# LogicPCB.net
KiCad netlist of a schematic drawn in EAGLE
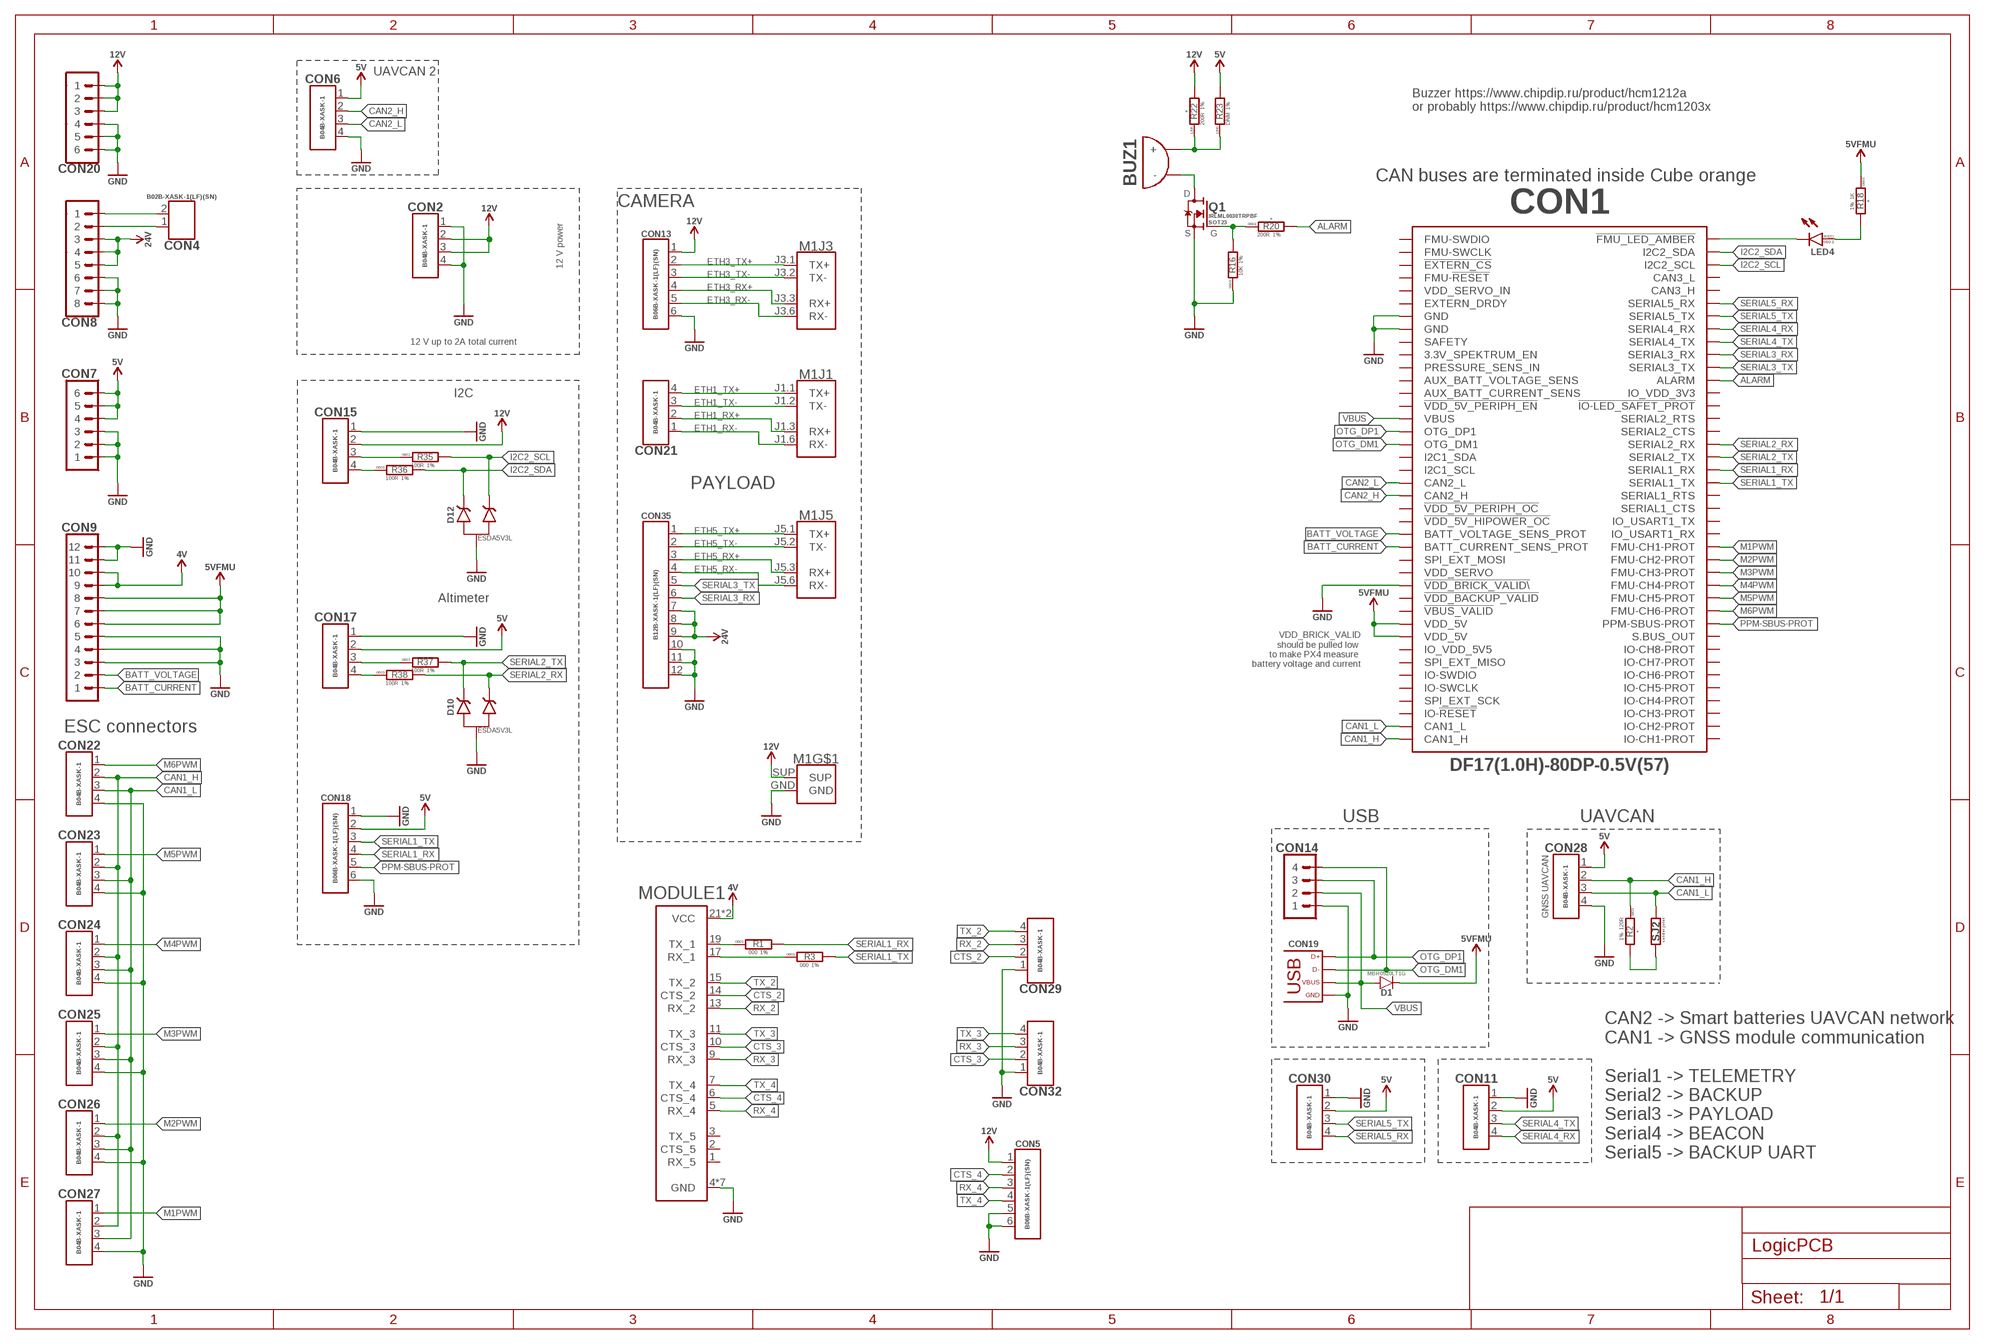
[diagram p0: schematic, sheet 1]

(export (version "E")
  (design (tool "Eeschema 10.0.6"))
  (components
    (comp (ref "BUZ1")
      (value "BUZZER-ЕР-12MM")
      (footprint "eagle-import:BUZZER_12MM")
      (fields (field (name "MANF") "JL World") (field (name "MANF#") "HCM1212A"))
      (libsource (lib "eagle-import") (part "BUZZER-ЕР-12MM"))
    )
    (comp (ref "CON1")
      (value "CUBE_ORANGE_")
      (footprint "eagle-import:CUBE_ORANGE")
      (fields (field (name "MANF#") "DF17(1.0H)-80DP-0.5V(57)") (field (name "MANF") "HIROSE"))
      (libsource (lib "eagle-import") (part "CUBE_ORANGE_"))
    )
    (comp (ref "CON2")
      (value "CON-4P-JST-XA")
      (footprint "eagle-import:B04B-XASK-1")
      (fields (field (name "MANF#") "B04B-XASK-1") (field (name "MANF") "JST Sales America"))
      (libsource (lib "eagle-import") (part "CON-4P-JST-XA"))
    )
    (comp (ref "CON4")
      (value "CON-2P-JST-XA")
      (footprint "eagle-import:B02B-XASK-1")
      (fields (field (name "MANF#") "B02B-XASK-1(LF)(SN)") (field (name "MANF") "JST Sales America"))
      (libsource (lib "eagle-import") (part "CON-2P-JST-XA"))
    )
    (comp (ref "CON5")
      (value "CON-6P-JST-XA")
      (footprint "eagle-import:B06B-XASK-1")
      (fields (field (name "MANF#") "B06B-XASK-1(LF)(SN)") (field (name "MANF") "JST Sales America"))
      (libsource (lib "eagle-import") (part "CON-6P-JST-XA"))
    )
    (comp (ref "CON6")
      (value "CON-4P-JST-XA")
      (footprint "eagle-import:B04B-XASK-1")
      (fields (field (name "MANF#") "B04B-XASK-1") (field (name "MANF") "JST Sales America"))
      (libsource (lib "eagle-import") (part "CON-4P-JST-XA"))
    )
    (comp (ref "CON7")
      (value "PINHEAD_1X06-2.54")
      (footprint "eagle-import:1X06-PTH-2.54")
      (libsource (lib "eagle-import") (part "PINHEAD_1X06-2.54"))
    )
    (comp (ref "CON8")
      (value "PINHEAD_1X08-2.54")
      (footprint "eagle-import:1X08-PTH-2.54")
      (libsource (lib "eagle-import") (part "PINHEAD_1X08-2.54"))
    )
    (comp (ref "CON9")
      (value "PINHEAD_1X12-2.54")
      (footprint "eagle-import:1X12-PTH-2.54")
      (libsource (lib "eagle-import") (part "PINHEAD_1X12-2.54"))
    )
    (comp (ref "CON11")
      (value "CON-4P-JST-XA")
      (footprint "eagle-import:B04B-XASK-1")
      (fields (field (name "MANF#") "B04B-XASK-1") (field (name "MANF") "JST Sales America"))
      (libsource (lib "eagle-import") (part "CON-4P-JST-XA"))
    )
    (comp (ref "CON13")
      (value "CON-6P-JST-XA")
      (footprint "eagle-import:B06B-XASK-1")
      (fields (field (name "MANF#") "B06B-XASK-1(LF)(SN)") (field (name "MANF") "JST Sales America"))
      (libsource (lib "eagle-import") (part "CON-6P-JST-XA"))
    )
    (comp (ref "CON14")
      (value "PINHEAD_1X04-2.54")
      (footprint "eagle-import:1X04-PTH-2.54")
      (libsource (lib "eagle-import") (part "PINHEAD_1X04-2.54"))
    )
    (comp (ref "CON15")
      (value "CON-4P-JST-XA")
      (footprint "eagle-import:B04B-XASK-1")
      (fields (field (name "MANF#") "B04B-XASK-1") (field (name "MANF") "JST Sales America"))
      (libsource (lib "eagle-import") (part "CON-4P-JST-XA"))
    )
    (comp (ref "CON17")
      (value "CON-4P-JST-XA")
      (footprint "eagle-import:B04B-XASK-1")
      (fields (field (name "MANF#") "B04B-XASK-1") (field (name "MANF") "JST Sales America"))
      (libsource (lib "eagle-import") (part "CON-4P-JST-XA"))
    )
    (comp (ref "CON18")
      (value "CON-6P-JST-XA")
      (footprint "eagle-import:B06B-XASK-1")
      (fields (field (name "MANF#") "B06B-XASK-1(LF)(SN)") (field (name "MANF") "JST Sales America"))
      (libsource (lib "eagle-import") (part "CON-6P-JST-XA"))
    )
    (comp (ref "CON19")
      (value "USB-TYPE-C-VERT-PROD")
      (footprint "eagle-import:2047110001-PROD")
      (fields (field (name "MANF") "Molex"))
      (libsource (lib "eagle-import") (part "USB-TYPE-C-VERT-PROD"))
    )
    (comp (ref "CON20")
      (value "PINHEAD_1X06-2.54")
      (footprint "eagle-import:1X06-PTH-2.54")
      (libsource (lib "eagle-import") (part "PINHEAD_1X06-2.54"))
    )
    (comp (ref "CON21")
      (value "CON-4P-JST-XA")
      (footprint "eagle-import:B04B-XASK-1")
      (fields (field (name "MANF#") "B04B-XASK-1") (field (name "MANF") "JST Sales America"))
      (libsource (lib "eagle-import") (part "CON-4P-JST-XA"))
    )
    (comp (ref "CON22")
      (value "CON-4P-JST-XA")
      (footprint "eagle-import:B04B-XASK-1")
      (fields (field (name "MANF#") "B04B-XASK-1") (field (name "MANF") "JST Sales America"))
      (libsource (lib "eagle-import") (part "CON-4P-JST-XA"))
    )
    (comp (ref "CON23")
      (value "CON-4P-JST-XA")
      (footprint "eagle-import:B04B-XASK-1")
      (fields (field (name "MANF#") "B04B-XASK-1") (field (name "MANF") "JST Sales America"))
      (libsource (lib "eagle-import") (part "CON-4P-JST-XA"))
    )
    (comp (ref "CON24")
      (value "CON-4P-JST-XA")
      (footprint "eagle-import:B04B-XASK-1")
      (fields (field (name "MANF#") "B04B-XASK-1") (field (name "MANF") "JST Sales America"))
      (libsource (lib "eagle-import") (part "CON-4P-JST-XA"))
    )
    (comp (ref "CON25")
      (value "CON-4P-JST-XA")
      (footprint "eagle-import:B04B-XASK-1")
      (fields (field (name "MANF#") "B04B-XASK-1") (field (name "MANF") "JST Sales America"))
      (libsource (lib "eagle-import") (part "CON-4P-JST-XA"))
    )
    (comp (ref "CON26")
      (value "CON-4P-JST-XA")
      (footprint "eagle-import:B04B-XASK-1")
      (fields (field (name "MANF#") "B04B-XASK-1") (field (name "MANF") "JST Sales America"))
      (libsource (lib "eagle-import") (part "CON-4P-JST-XA"))
    )
    (comp (ref "CON27")
      (value "CON-4P-JST-XA")
      (footprint "eagle-import:B04B-XASK-1")
      (fields (field (name "MANF#") "B04B-XASK-1") (field (name "MANF") "JST Sales America"))
      (libsource (lib "eagle-import") (part "CON-4P-JST-XA"))
    )
    (comp (ref "CON28")
      (value "CON-4P-JST-XA")
      (footprint "eagle-import:B04B-XASK-1")
      (fields (field (name "MANF#") "B04B-XASK-1") (field (name "MANF") "JST Sales America"))
      (libsource (lib "eagle-import") (part "CON-4P-JST-XA"))
    )
    (comp (ref "CON29")
      (value "CON-4P-JST-XA")
      (footprint "eagle-import:B04B-XASK-1")
      (fields (field (name "MANF#") "B04B-XASK-1") (field (name "MANF") "JST Sales America"))
      (libsource (lib "eagle-import") (part "CON-4P-JST-XA"))
    )
    (comp (ref "CON30")
      (value "CON-4P-JST-XA")
      (footprint "eagle-import:B04B-XASK-1")
      (fields (field (name "MANF#") "B04B-XASK-1") (field (name "MANF") "JST Sales America"))
      (libsource (lib "eagle-import") (part "CON-4P-JST-XA"))
    )
    (comp (ref "CON32")
      (value "CON-4P-JST-XA")
      (footprint "eagle-import:B04B-XASK-1")
      (fields (field (name "MANF#") "B04B-XASK-1") (field (name "MANF") "JST Sales America"))
      (libsource (lib "eagle-import") (part "CON-4P-JST-XA"))
    )
    (comp (ref "CON35")
      (value "CON-12P-JST-XA")
      (footprint "eagle-import:B12B-XASK-1")
      (fields (field (name "MANF#") "B12B-XASK-1(LF)(SN)") (field (name "MANF") "JST Sales America"))
      (libsource (lib "eagle-import") (part "CON-12P-JST-XA"))
    )
    (comp (ref "D1")
      (value "MBR0520L-SOD123")
      (footprint "eagle-import:SOD123")
      (fields (field (name "MANF#") "MBR0520LT1G") (field (name "MANF") "ON Semiconductor"))
      (libsource (lib "eagle-import") (part "MBR0520L-SOD123"))
    )
    (comp (ref "D10")
      (value "ESDA5V3L")
      (footprint "eagle-import:SOT23B-3")
      (fields (field (name "MANF#") "ESDA5V3L") (field (name "MANF") "STMicroelectronics"))
      (libsource (lib "eagle-import") (part "ESDA5V3L"))
    )
    (comp (ref "D12")
      (value "ESDA5V3L")
      (footprint "eagle-import:SOT23B-3")
      (fields (field (name "MANF#") "ESDA5V3L") (field (name "MANF") "STMicroelectronics"))
      (libsource (lib "eagle-import") (part "ESDA5V3L"))
    )
    (comp (ref "LED4")
      (value "LED-0603")
      (footprint "eagle-import:LED0603")
      (fields
        (field (name "PACKAGE") "0603")
        (field (name "COLOR") "RED")
        (field (name "LCSC#") "C2286")
        (field (name "MANF") "Hubei KENTO Elec")
        (field (name "MANF#") "KT-0603R")
      )
      (libsource (lib "eagle-import") (part "LED-0603"))
    )
    (comp (ref "M1")
      (value "05G_ETHERNET_SWITCH")
      (footprint "eagle-import:05G_ETH_SWITCH")
      (libsource (lib "eagle-import") (part "05G_ETHERNET_SWITCH"))
    )
    (comp (ref "MODULE1")
      (value "MODEM_CARRIER")
      (footprint "eagle-import:MODEM_CARRIER")
      (libsource (lib "eagle-import") (part "MODEM_CARRIER"))
    )
    (comp (ref "Q1")
      (value "IRLML0030")
      (footprint "eagle-import:SOT23")
      (fields
        (field (name "MANF#") "IRLML0030TRPBF")
        (field (name "PACKAGE") "SOT23")
        (field (name "MANF") "Infineon Technologies")
      )
      (libsource (lib "eagle-import") (part "IRLML0030"))
    )
    (comp (ref "R1")
      (value "000")
      (footprint "eagle-import:R0603")
      (fields (field (name "PACKAGE") "0603") (field (name "TOLERANCE") "1%"))
      (libsource (lib "eagle-import") (part "R-0603-1%"))
    )
    (comp (ref "R2")
      (value "120R")
      (footprint "eagle-import:R0603")
      (fields
        (field (name "PACKAGE") "0603")
        (field (name "TOLERANCE") "1%")
        (field (name "ALLOCATED") "+")
        (field (name "LCSC#") "C22787")
        (field (name "MANF") "UNI-ROYAL(Uniroyal Elec)")
        (field (name "MANF#") "0603WAF1200T5E")
      )
      (libsource (lib "eagle-import") (part "R-0603-1%"))
    )
    (comp (ref "R3")
      (value "000")
      (footprint "eagle-import:R0603")
      (fields (field (name "PACKAGE") "0603") (field (name "TOLERANCE") "1%"))
      (libsource (lib "eagle-import") (part "R-0603-1%"))
    )
    (comp (ref "R16")
      (value "10K")
      (footprint "eagle-import:R0603")
      (fields (field (name "PACKAGE") "0603") (field (name "TOLERANCE") "1%"))
      (libsource (lib "eagle-import") (part "R-0603-1%"))
    )
    (comp (ref "R18")
      (value "1K")
      (footprint "eagle-import:R0603")
      (fields
        (field (name "PACKAGE") "0603")
        (field (name "TOLERANCE") "1%")
        (field (name "ALLOCATED") "+")
        (field (name "LCSC#") "C21190")
        (field (name "MANF") "UNI-ROYAL(Uniroyal Elec)")
        (field (name "MANF#") "0603WAF1001T5E")
      )
      (libsource (lib "eagle-import") (part "R-0603-1%"))
    )
    (comp (ref "R20")
      (value "200R")
      (footprint "eagle-import:R0603")
      (fields
        (field (name "PACKAGE") "0603")
        (field (name "TOLERANCE") "1%")
        (field (name "ALLOCATED") "+")
        (field (name "LCSC#") "C21190")
        (field (name "MANF") "UNI-ROYAL(Uniroyal Elec)")
        (field (name "MANF#") "0603WAF1001T5E")
      )
      (libsource (lib "eagle-import") (part "R-0603-1%"))
    )
    (comp (ref "R22")
      (value "200R")
      (footprint "eagle-import:R1206")
      (fields
        (field (name "PACKAGE") "1206")
        (field (name "TOLERANCE") "1%")
        (field (name "ALLOCATED") "+")
        (field (name "LCSC#") "C25361")
        (field (name "MANF") "UNI-ROYAL")
        (field (name "MANF#") "1206W4J0201T5E")
      )
      (libsource (lib "eagle-import") (part "R-1206-1%"))
    )
    (comp (ref "R23")
      (value "DNM")
      (footprint "eagle-import:R1206")
      (fields (field (name "PACKAGE") "1206") (field (name "TOLERANCE") "1%"))
      (libsource (lib "eagle-import") (part "R-1206-1%"))
    )
    (comp (ref "R35")
      (value "100R")
      (footprint "eagle-import:R0603")
      (fields (field (name "PACKAGE") "0603") (field (name "TOLERANCE") "1%"))
      (libsource (lib "eagle-import") (part "R-0603-1%"))
    )
    (comp (ref "R36")
      (value "100R")
      (footprint "eagle-import:R0603")
      (fields (field (name "PACKAGE") "0603") (field (name "TOLERANCE") "1%"))
      (libsource (lib "eagle-import") (part "R-0603-1%"))
    )
    (comp (ref "R37")
      (value "100R")
      (footprint "eagle-import:R0603")
      (fields (field (name "PACKAGE") "0603") (field (name "TOLERANCE") "1%"))
      (libsource (lib "eagle-import") (part "R-0603-1%"))
    )
    (comp (ref "R38")
      (value "100R")
      (footprint "eagle-import:R0603")
      (fields (field (name "PACKAGE") "0603") (field (name "TOLERANCE") "1%"))
      (libsource (lib "eagle-import") (part "R-0603-1%"))
    )
    (comp (ref "SJ2")
      (value "SOLDER_JOINT-SJ1")
      (footprint "eagle-import:RES_0")
      (libsource (lib "eagle-import") (part "SOLDER_JOINT-SJ1"))
    )
  )
  (nets
    (net (code "1") (name "/ETH1_RX+") (class "Default")
      (node (ref "CON21") (pin "2") (pinfunction "2_2") (pintype "bidirectional"))
      (node (ref "M1") (pin "J1.3") (pinfunction "RX+_J1.3") (pintype "bidirectional"))
    )
    (net (code "2") (name "/ETH1_RX-") (class "Default")
      (node (ref "CON21") (pin "1") (pinfunction "1_1") (pintype "bidirectional"))
      (node (ref "M1") (pin "J1.6") (pinfunction "RX-_J1.6") (pintype "bidirectional"))
    )
    (net (code "3") (name "/ETH1_TX+") (class "Default")
      (node (ref "CON21") (pin "4") (pinfunction "4_4") (pintype "bidirectional"))
      (node (ref "M1") (pin "J1.1") (pinfunction "TX+_J1.1") (pintype "bidirectional"))
    )
    (net (code "4") (name "/ETH1_TX-") (class "Default")
      (node (ref "CON21") (pin "3") (pinfunction "3_3") (pintype "bidirectional"))
      (node (ref "M1") (pin "J1.2") (pinfunction "TX-_J1.2") (pintype "bidirectional"))
    )
    (net (code "5") (name "/ETH3_RX+") (class "Default")
      (node (ref "CON13") (pin "4") (pinfunction "4_4") (pintype "bidirectional"))
      (node (ref "M1") (pin "J3.3") (pinfunction "RX+_J3.3") (pintype "bidirectional"))
    )
    (net (code "6") (name "/ETH3_RX-") (class "Default")
      (node (ref "CON13") (pin "5") (pinfunction "5_5") (pintype "bidirectional"))
      (node (ref "M1") (pin "J3.6") (pinfunction "RX-_J3.6") (pintype "bidirectional"))
    )
    (net (code "7") (name "/ETH3_TX+") (class "Default")
      (node (ref "CON13") (pin "2") (pinfunction "2_2") (pintype "bidirectional"))
      (node (ref "M1") (pin "J3.1") (pinfunction "TX+_J3.1") (pintype "bidirectional"))
    )
    (net (code "8") (name "/ETH3_TX-") (class "Default")
      (node (ref "CON13") (pin "3") (pinfunction "3_3") (pintype "bidirectional"))
      (node (ref "M1") (pin "J3.2") (pinfunction "TX-_J3.2") (pintype "bidirectional"))
    )
    (net (code "9") (name "/ETH5_RX+") (class "Default")
      (node (ref "CON35") (pin "3") (pinfunction "3_3") (pintype "bidirectional"))
      (node (ref "M1") (pin "J5.3") (pinfunction "RX+_J5.3") (pintype "bidirectional"))
    )
    (net (code "10") (name "/ETH5_RX-") (class "Default")
      (node (ref "CON35") (pin "4") (pinfunction "4_4") (pintype "bidirectional"))
      (node (ref "M1") (pin "J5.6") (pinfunction "RX-_J5.6") (pintype "bidirectional"))
    )
    (net (code "11") (name "/ETH5_TX+") (class "Default")
      (node (ref "CON35") (pin "1") (pinfunction "1_1") (pintype "bidirectional"))
      (node (ref "M1") (pin "J5.1") (pinfunction "TX+_J5.1") (pintype "bidirectional"))
    )
    (net (code "12") (name "/ETH5_TX-") (class "Default")
      (node (ref "CON35") (pin "2") (pinfunction "2_2") (pintype "bidirectional"))
      (node (ref "M1") (pin "J5.2") (pinfunction "TX-_J5.2") (pintype "bidirectional"))
    )
    (net (code "13") (name "4V") (class "Default")
      (node (ref "CON9") (pin "10") (pinfunction "10_10") (pintype "passive"))
      (node (ref "CON9") (pin "9") (pinfunction "9_9") (pintype "passive"))
      (node (ref "MODULE1") (pin "21") (pinfunction "VCC_21") (pintype "bidirectional"))
      (node (ref "MODULE1") (pin "23") (pinfunction "VCC_23") (pintype "bidirectional"))
    )
    (net (code "14") (name "5V") (class "Default")
      (node (ref "CON11") (pin "2") (pinfunction "2_2") (pintype "bidirectional"))
      (node (ref "CON17") (pin "2") (pinfunction "2_2") (pintype "bidirectional"))
      (node (ref "CON18") (pin "2") (pinfunction "2_2") (pintype "bidirectional"))
      (node (ref "CON28") (pin "1") (pinfunction "1_1") (pintype "bidirectional"))
      (node (ref "CON30") (pin "2") (pinfunction "2_2") (pintype "bidirectional"))
      (node (ref "CON6") (pin "1") (pinfunction "1_1") (pintype "bidirectional"))
      (node (ref "CON7") (pin "4") (pinfunction "4_4") (pintype "passive"))
      (node (ref "CON7") (pin "5") (pinfunction "5_5") (pintype "passive"))
      (node (ref "CON7") (pin "6") (pinfunction "6_6") (pintype "passive"))
      (node (ref "R23") (pin "P$2") (pinfunction "2_P$2") (pintype "passive"))
    )
    (net (code "15") (name "5VFMU") (class "Default")
      (node (ref "CON1") (pin "61") (pinfunction "VDD_5V_61") (pintype "bidirectional"))
      (node (ref "CON1") (pin "63") (pinfunction "VDD_5V_63") (pintype "bidirectional"))
      (node (ref "CON9") (pin "6") (pinfunction "6_6") (pintype "passive"))
      (node (ref "CON9") (pin "7") (pinfunction "7_7") (pintype "passive"))
      (node (ref "CON9") (pin "8") (pinfunction "8_8") (pintype "passive"))
      (node (ref "D1") (pin "C") (pinfunction "C_C") (pintype "passive"))
      (node (ref "R18") (pin "1") (pinfunction "1_1") (pintype "passive"))
    )
    (net (code "16") (name "12V") (class "Default")
      (node (ref "CON13") (pin "1") (pinfunction "1_1") (pintype "bidirectional"))
      (node (ref "CON15") (pin "2") (pinfunction "2_2") (pintype "bidirectional"))
      (node (ref "CON2") (pin "2") (pinfunction "2_2") (pintype "bidirectional"))
      (node (ref "CON2") (pin "3") (pinfunction "3_3") (pintype "bidirectional"))
      (node (ref "CON20") (pin "1") (pinfunction "1_1") (pintype "passive"))
      (node (ref "CON20") (pin "2") (pinfunction "2_2") (pintype "passive"))
      (node (ref "CON20") (pin "3") (pinfunction "3_3") (pintype "passive"))
      (node (ref "CON5") (pin "1") (pinfunction "1_1") (pintype "bidirectional"))
      (node (ref "M1") (pin "SUP") (pinfunction "SUP_SUP") (pintype "bidirectional"))
      (node (ref "R22") (pin "P$2") (pinfunction "2_P$2") (pintype "passive"))
    )
    (net (code "17") (name "24V") (class "Default")
      (node (ref "CON35") (pin "7") (pinfunction "7_7") (pintype "bidirectional"))
      (node (ref "CON35") (pin "8") (pinfunction "8_8") (pintype "bidirectional"))
      (node (ref "CON35") (pin "9") (pinfunction "9_9") (pintype "bidirectional"))
      (node (ref "CON8") (pin "3") (pinfunction "3_3") (pintype "passive"))
      (node (ref "CON8") (pin "4") (pinfunction "4_4") (pintype "passive"))
      (node (ref "CON8") (pin "5") (pinfunction "5_5") (pintype "passive"))
    )
    (net (code "18") (name "ALARM") (class "Default")
      (node (ref "CON1") (pin "24") (pinfunction "ALARM_24") (pintype "bidirectional"))
      (node (ref "R20") (pin "2") (pinfunction "2_2") (pintype "passive"))
    )
    (net (code "19") (name "BATT_CURRENT") (class "Default")
      (node (ref "CON1") (pin "49") (pinfunction "BATT_CURRENT_SENS_PROT_49") (pintype "bidirectional"))
      (node (ref "CON9") (pin "1") (pinfunction "1_1") (pintype "passive"))
    )
    (net (code "20") (name "BATT_VOLTAGE") (class "Default")
      (node (ref "CON1") (pin "47") (pinfunction "BATT_VOLTAGE_SENS_PROT_47") (pintype "bidirectional"))
      (node (ref "CON9") (pin "2") (pinfunction "2_2") (pintype "passive"))
    )
    (net (code "21") (name "CAN1_H") (class "Default")
      (node (ref "CON1") (pin "79") (pinfunction "CAN1_H_79") (pintype "bidirectional"))
      (node (ref "CON22") (pin "2") (pinfunction "2_2") (pintype "bidirectional"))
      (node (ref "CON23") (pin "2") (pinfunction "2_2") (pintype "bidirectional"))
      (node (ref "CON24") (pin "2") (pinfunction "2_2") (pintype "bidirectional"))
      (node (ref "CON25") (pin "2") (pinfunction "2_2") (pintype "bidirectional"))
      (node (ref "CON26") (pin "2") (pinfunction "2_2") (pintype "bidirectional"))
      (node (ref "CON27") (pin "2") (pinfunction "2_2") (pintype "bidirectional"))
      (node (ref "CON28") (pin "2") (pinfunction "2_2") (pintype "bidirectional"))
      (node (ref "R2") (pin "1") (pinfunction "1_1") (pintype "passive"))
    )
    (net (code "22") (name "CAN1_L") (class "Default")
      (node (ref "CON1") (pin "77") (pinfunction "CAN1_L_77") (pintype "bidirectional"))
      (node (ref "CON22") (pin "3") (pinfunction "3_3") (pintype "bidirectional"))
      (node (ref "CON23") (pin "3") (pinfunction "3_3") (pintype "bidirectional"))
      (node (ref "CON24") (pin "3") (pinfunction "3_3") (pintype "bidirectional"))
      (node (ref "CON25") (pin "3") (pinfunction "3_3") (pintype "bidirectional"))
      (node (ref "CON26") (pin "3") (pinfunction "3_3") (pintype "bidirectional"))
      (node (ref "CON27") (pin "3") (pinfunction "3_3") (pintype "bidirectional"))
      (node (ref "CON28") (pin "3") (pinfunction "3_3") (pintype "bidirectional"))
      (node (ref "SJ2") (pin "2") (pinfunction "2_2") (pintype "passive"))
    )
    (net (code "23") (name "CAN2_H") (class "Default")
      (node (ref "CON1") (pin "41") (pinfunction "CAN2_H_41") (pintype "bidirectional"))
      (node (ref "CON6") (pin "2") (pinfunction "2_2") (pintype "bidirectional"))
    )
    (net (code "24") (name "CAN2_L") (class "Default")
      (node (ref "CON1") (pin "39") (pinfunction "CAN2_L_39") (pintype "bidirectional"))
      (node (ref "CON6") (pin "3") (pinfunction "3_3") (pintype "bidirectional"))
    )
    (net (code "25") (name "CTS_2") (class "Default")
      (node (ref "CON29") (pin "2") (pinfunction "2_2") (pintype "bidirectional"))
      (node (ref "MODULE1") (pin "14") (pinfunction "CTS_2_14") (pintype "bidirectional"))
    )
    (net (code "26") (name "CTS_3") (class "Default")
      (node (ref "CON32") (pin "2") (pinfunction "2_2") (pintype "bidirectional"))
      (node (ref "MODULE1") (pin "10") (pinfunction "CTS_3_10") (pintype "bidirectional"))
    )
    (net (code "27") (name "CTS_4") (class "Default")
      (node (ref "CON5") (pin "2") (pinfunction "2_2") (pintype "bidirectional"))
      (node (ref "MODULE1") (pin "6") (pinfunction "CTS_4_6") (pintype "bidirectional"))
    )
    (net (code "28") (name "GND") (class "Default")
      (node (ref "CON1") (pin "13") (pinfunction "GND_13") (pintype "bidirectional"))
      (node (ref "CON1") (pin "15") (pinfunction "GND_15") (pintype "bidirectional"))
      (node (ref "CON1") (pin "55") (pinfunction "~{VDD_BRICK_VALID\\}_55") (pintype "bidirectional"))
      (node (ref "CON11") (pin "1") (pinfunction "1_1") (pintype "bidirectional"))
      (node (ref "CON13") (pin "6") (pinfunction "6_6") (pintype "bidirectional"))
      (node (ref "CON14") (pin "1") (pinfunction "1_1") (pintype "passive"))
      (node (ref "CON15") (pin "1") (pinfunction "1_1") (pintype "bidirectional"))
      (node (ref "CON17") (pin "1") (pinfunction "1_1") (pintype "bidirectional"))
      (node (ref "CON18") (pin "1") (pinfunction "1_1") (pintype "bidirectional"))
      (node (ref "CON18") (pin "6") (pinfunction "6_6") (pintype "bidirectional"))
      (node (ref "CON19") (pin "A1") (pinfunction "GND_A1") (pintype "bidirectional"))
      (node (ref "CON19") (pin "A12") (pinfunction "GND_A12") (pintype "bidirectional"))
      (node (ref "CON19") (pin "B1") (pinfunction "GND_B1") (pintype "bidirectional"))
      (node (ref "CON19") (pin "B12") (pinfunction "GND_B12") (pintype "bidirectional"))
      (node (ref "CON19") (pin "G1") (pinfunction "GND_G1") (pintype "bidirectional"))
      (node (ref "CON19") (pin "G10") (pinfunction "GND_G10") (pintype "bidirectional"))
      (node (ref "CON19") (pin "G2") (pinfunction "GND_G2") (pintype "bidirectional"))
      (node (ref "CON19") (pin "G4") (pinfunction "GND_G4") (pintype "bidirectional"))
      (node (ref "CON19") (pin "G5") (pinfunction "GND_G5") (pintype "bidirectional"))
      (node (ref "CON19") (pin "G7") (pinfunction "GND_G7") (pintype "bidirectional"))
      (node (ref "CON19") (pin "G8") (pinfunction "GND_G8") (pintype "bidirectional"))
      (node (ref "CON19") (pin "G9") (pinfunction "GND_G9") (pintype "bidirectional"))
      (node (ref "CON19") (pin "P$1") (pinfunction "GND_P$1") (pintype "bidirectional"))
      (node (ref "CON19") (pin "P$2") (pinfunction "GND_P$2") (pintype "bidirectional"))
      (node (ref "CON2") (pin "1") (pinfunction "1_1") (pintype "bidirectional"))
      (node (ref "CON2") (pin "4") (pinfunction "4_4") (pintype "bidirectional"))
      (node (ref "CON20") (pin "4") (pinfunction "4_4") (pintype "passive"))
      (node (ref "CON20") (pin "5") (pinfunction "5_5") (pintype "passive"))
      (node (ref "CON20") (pin "6") (pinfunction "6_6") (pintype "passive"))
      (node (ref "CON22") (pin "4") (pinfunction "4_4") (pintype "bidirectional"))
      (node (ref "CON23") (pin "4") (pinfunction "4_4") (pintype "bidirectional"))
      (node (ref "CON24") (pin "4") (pinfunction "4_4") (pintype "bidirectional"))
      (node (ref "CON25") (pin "4") (pinfunction "4_4") (pintype "bidirectional"))
      (node (ref "CON26") (pin "4") (pinfunction "4_4") (pintype "bidirectional"))
      (node (ref "CON27") (pin "4") (pinfunction "4_4") (pintype "bidirectional"))
      (node (ref "CON28") (pin "4") (pinfunction "4_4") (pintype "bidirectional"))
      (node (ref "CON29") (pin "1") (pinfunction "1_1") (pintype "bidirectional"))
      (node (ref "CON30") (pin "1") (pinfunction "1_1") (pintype "bidirectional"))
      (node (ref "CON32") (pin "1") (pinfunction "1_1") (pintype "bidirectional"))
      (node (ref "CON35") (pin "10") (pinfunction "10_10") (pintype "bidirectional"))
      (node (ref "CON35") (pin "11") (pinfunction "11_11") (pintype "bidirectional"))
      (node (ref "CON35") (pin "12") (pinfunction "12_12") (pintype "bidirectional"))
      (node (ref "CON5") (pin "5") (pinfunction "5_5") (pintype "bidirectional"))
      (node (ref "CON5") (pin "6") (pinfunction "6_6") (pintype "bidirectional"))
      (node (ref "CON6") (pin "4") (pinfunction "4_4") (pintype "bidirectional"))
      (node (ref "CON7") (pin "1") (pinfunction "1_1") (pintype "passive"))
      (node (ref "CON7") (pin "2") (pinfunction "2_2") (pintype "passive"))
      (node (ref "CON7") (pin "3") (pinfunction "3_3") (pintype "passive"))
      (node (ref "CON8") (pin "6") (pinfunction "6_6") (pintype "passive"))
      (node (ref "CON8") (pin "7") (pinfunction "7_7") (pintype "passive"))
      (node (ref "CON8") (pin "8") (pinfunction "8_8") (pintype "passive"))
      (node (ref "CON9") (pin "11") (pinfunction "11_11") (pintype "passive"))
      (node (ref "CON9") (pin "12") (pinfunction "12_12") (pintype "passive"))
      (node (ref "CON9") (pin "3") (pinfunction "3_3") (pintype "passive"))
      (node (ref "CON9") (pin "4") (pinfunction "4_4") (pintype "passive"))
      (node (ref "CON9") (pin "5") (pinfunction "5_5") (pintype "passive"))
      (node (ref "D10") (pin "3") (pinfunction "A_3") (pintype "bidirectional"))
      (node (ref "D12") (pin "3") (pinfunction "A_3") (pintype "bidirectional"))
      (node (ref "M1") (pin "GND") (pinfunction "GND_GND") (pintype "bidirectional"))
      (node (ref "MODULE1") (pin "12") (pinfunction "GND_12") (pintype "bidirectional"))
      (node (ref "MODULE1") (pin "16") (pinfunction "GND_16") (pintype "bidirectional"))
      (node (ref "MODULE1") (pin "20") (pinfunction "GND_20") (pintype "bidirectional"))
      (node (ref "MODULE1") (pin "22") (pinfunction "GND_22") (pintype "bidirectional"))
      (node (ref "MODULE1") (pin "24") (pinfunction "GND_24") (pintype "bidirectional"))
      (node (ref "MODULE1") (pin "4") (pinfunction "GND_4") (pintype "bidirectional"))
      (node (ref "MODULE1") (pin "8") (pinfunction "GND_8") (pintype "bidirectional"))
      (node (ref "Q1") (pin "2") (pinfunction "S_2") (pintype "passive"))
      (node (ref "R16") (pin "1") (pinfunction "1_1") (pintype "passive"))
    )
    (net (code "29") (name "I2C2_SCL") (class "Default")
      (node (ref "CON1") (pin "6") (pinfunction "I2C2_SCL_6") (pintype "bidirectional"))
      (node (ref "D12") (pin "2") (pinfunction "C1_2") (pintype "bidirectional"))
      (node (ref "R35") (pin "2") (pinfunction "2_2") (pintype "passive"))
    )
    (net (code "30") (name "I2C2_SDA") (class "Default")
      (node (ref "CON1") (pin "4") (pinfunction "I2C2_SDA_4") (pintype "bidirectional"))
      (node (ref "D12") (pin "1") (pinfunction "C_1") (pintype "bidirectional"))
      (node (ref "R36") (pin "2") (pinfunction "2_2") (pintype "passive"))
    )
    (net (code "31") (name "M1PWM") (class "Default")
      (node (ref "CON1") (pin "50") (pinfunction "FMU-CH1-PROT_50") (pintype "bidirectional"))
      (node (ref "CON27") (pin "1") (pinfunction "1_1") (pintype "bidirectional"))
    )
    (net (code "32") (name "M2PWM") (class "Default")
      (node (ref "CON1") (pin "52") (pinfunction "FMU-CH2-PROT_52") (pintype "bidirectional"))
      (node (ref "CON26") (pin "1") (pinfunction "1_1") (pintype "bidirectional"))
    )
    (net (code "33") (name "M3PWM") (class "Default")
      (node (ref "CON1") (pin "54") (pinfunction "FMU-CH3-PROT_54") (pintype "bidirectional"))
      (node (ref "CON25") (pin "1") (pinfunction "1_1") (pintype "bidirectional"))
    )
    (net (code "34") (name "M4PWM") (class "Default")
      (node (ref "CON1") (pin "56") (pinfunction "FMU-CH4-PROT_56") (pintype "bidirectional"))
      (node (ref "CON24") (pin "1") (pinfunction "1_1") (pintype "bidirectional"))
    )
    (net (code "35") (name "M5PWM") (class "Default")
      (node (ref "CON1") (pin "58") (pinfunction "FMU-CH5-PROT_58") (pintype "bidirectional"))
      (node (ref "CON23") (pin "1") (pinfunction "1_1") (pintype "bidirectional"))
    )
    (net (code "36") (name "M6PWM") (class "Default")
      (node (ref "CON1") (pin "60") (pinfunction "FMU-CH6-PROT_60") (pintype "bidirectional"))
      (node (ref "CON22") (pin "1") (pinfunction "1_1") (pintype "bidirectional"))
    )
    (net (code "37") (name "Net-(BUZ1-+)") (class "Default")
      (node (ref "BUZ1") (pin "1") (pinfunction "+_1") (pintype "bidirectional"))
      (node (ref "R22") (pin "P$1") (pinfunction "1_P$1") (pintype "passive"))
      (node (ref "R23") (pin "P$1") (pinfunction "1_P$1") (pintype "passive"))
    )
    (net (code "38") (name "Net-(BUZ1--)") (class "Default")
      (node (ref "BUZ1") (pin "2") (pinfunction "-_2") (pintype "bidirectional"))
      (node (ref "Q1") (pin "3") (pinfunction "D_3") (pintype "passive"))
    )
    (net (code "39") (name "Net-(CON1-~{FMU_LED_AMBER})") (class "Default")
      (node (ref "CON1") (pin "2") (pinfunction "~{FMU_LED_AMBER}_2") (pintype "bidirectional"))
      (node (ref "LED4") (pin "C") (pinfunction "C_C") (pintype "bidirectional"))
    )
    (net (code "40") (name "Net-(CON4-Pad1)") (class "Default")
      (node (ref "CON4") (pin "1") (pinfunction "1_1") (pintype "bidirectional"))
      (node (ref "CON8") (pin "2") (pinfunction "2_2") (pintype "passive"))
    )
    (net (code "41") (name "Net-(CON4-Pad2)") (class "Default")
      (node (ref "CON4") (pin "2") (pinfunction "2_2") (pintype "bidirectional"))
      (node (ref "CON8") (pin "1") (pinfunction "1_1") (pintype "passive"))
    )
    (net (code "42") (name "Net-(CON15-Pad3)") (class "Default")
      (node (ref "CON15") (pin "3") (pinfunction "3_3") (pintype "bidirectional"))
      (node (ref "R35") (pin "1") (pinfunction "1_1") (pintype "passive"))
    )
    (net (code "43") (name "Net-(CON15-Pad4)") (class "Default")
      (node (ref "CON15") (pin "4") (pinfunction "4_4") (pintype "bidirectional"))
      (node (ref "R36") (pin "1") (pinfunction "1_1") (pintype "passive"))
    )
    (net (code "44") (name "Net-(CON17-Pad3)") (class "Default")
      (node (ref "CON17") (pin "3") (pinfunction "3_3") (pintype "bidirectional"))
      (node (ref "R37") (pin "1") (pinfunction "1_1") (pintype "passive"))
    )
    (net (code "45") (name "Net-(CON17-Pad4)") (class "Default")
      (node (ref "CON17") (pin "4") (pinfunction "4_4") (pintype "bidirectional"))
      (node (ref "R38") (pin "1") (pinfunction "1_1") (pintype "passive"))
    )
    (net (code "46") (name "Net-(LED4-PadA)") (class "Default")
      (node (ref "LED4") (pin "A") (pinfunction "A_A") (pintype "bidirectional"))
      (node (ref "R18") (pin "2") (pinfunction "2_2") (pintype "passive"))
    )
    (net (code "47") (name "Net-(MODULE1-RX_1)") (class "Default")
      (node (ref "MODULE1") (pin "17") (pinfunction "RX_1_17") (pintype "bidirectional"))
      (node (ref "R3") (pin "1") (pinfunction "1_1") (pintype "passive"))
    )
    (net (code "48") (name "Net-(MODULE1-TX_1)") (class "Default")
      (node (ref "MODULE1") (pin "19") (pinfunction "TX_1_19") (pintype "bidirectional"))
      (node (ref "R1") (pin "1") (pinfunction "1_1") (pintype "passive"))
    )
    (net (code "49") (name "Net-(Q1-G)") (class "Default")
      (node (ref "Q1") (pin "1") (pinfunction "G_1") (pintype "passive"))
      (node (ref "R16") (pin "2") (pinfunction "2_2") (pintype "passive"))
      (node (ref "R20") (pin "1") (pinfunction "1_1") (pintype "passive"))
    )
    (net (code "50") (name "Net-(R2-Pad2)") (class "Default")
      (node (ref "R2") (pin "2") (pinfunction "2_2") (pintype "passive"))
      (node (ref "SJ2") (pin "1") (pinfunction "1_1") (pintype "passive"))
    )
    (net (code "51") (name "OTG_DM1") (class "Default")
      (node (ref "CON1") (pin "33") (pinfunction "OTG_DM1_33") (pintype "bidirectional"))
      (node (ref "CON14") (pin "4") (pinfunction "4_4") (pintype "passive"))
      (node (ref "CON19") (pin "A7") (pinfunction "D-_A7") (pintype "bidirectional"))
      (node (ref "CON19") (pin "B7") (pinfunction "D-_B7") (pintype "bidirectional"))
    )
    (net (code "52") (name "OTG_DP1") (class "Default")
      (node (ref "CON1") (pin "31") (pinfunction "OTG_DP1_31") (pintype "bidirectional"))
      (node (ref "CON14") (pin "3") (pinfunction "3_3") (pintype "passive"))
      (node (ref "CON19") (pin "A6") (pinfunction "D+_A6") (pintype "bidirectional"))
      (node (ref "CON19") (pin "B6") (pinfunction "D+_B6") (pintype "bidirectional"))
    )
    (net (code "53") (name "PPM-SBUS-PROT") (class "Default")
      (node (ref "CON1") (pin "62") (pinfunction "PPM-SBUS-PROT_62") (pintype "bidirectional"))
      (node (ref "CON18") (pin "5") (pinfunction "5_5") (pintype "bidirectional"))
    )
    (net (code "54") (name "RX_2") (class "Default")
      (node (ref "CON29") (pin "3") (pinfunction "3_3") (pintype "bidirectional"))
      (node (ref "MODULE1") (pin "13") (pinfunction "RX_2_13") (pintype "bidirectional"))
    )
    (net (code "55") (name "RX_3") (class "Default")
      (node (ref "CON32") (pin "3") (pinfunction "3_3") (pintype "bidirectional"))
      (node (ref "MODULE1") (pin "9") (pinfunction "RX_3_9") (pintype "bidirectional"))
    )
    (net (code "56") (name "RX_4") (class "Default")
      (node (ref "CON5") (pin "3") (pinfunction "3_3") (pintype "bidirectional"))
      (node (ref "MODULE1") (pin "5") (pinfunction "RX_4_5") (pintype "bidirectional"))
    )
    (net (code "57") (name "SERIAL1_RX") (class "Default")
      (node (ref "CON1") (pin "38") (pinfunction "SERIAL1_RX_38") (pintype "bidirectional"))
      (node (ref "CON18") (pin "4") (pinfunction "4_4") (pintype "bidirectional"))
      (node (ref "R1") (pin "2") (pinfunction "2_2") (pintype "passive"))
    )
    (net (code "58") (name "SERIAL1_TX") (class "Default")
      (node (ref "CON1") (pin "40") (pinfunction "SERIAL1_TX_40") (pintype "bidirectional"))
      (node (ref "CON18") (pin "3") (pinfunction "3_3") (pintype "bidirectional"))
      (node (ref "R3") (pin "2") (pinfunction "2_2") (pintype "passive"))
    )
    (net (code "59") (name "SERIAL2_RX") (class "Default")
      (node (ref "CON1") (pin "34") (pinfunction "SERIAL2_RX_34") (pintype "bidirectional"))
      (node (ref "D10") (pin "2") (pinfunction "C1_2") (pintype "bidirectional"))
      (node (ref "R38") (pin "2") (pinfunction "2_2") (pintype "passive"))
    )
    (net (code "60") (name "SERIAL2_TX") (class "Default")
      (node (ref "CON1") (pin "36") (pinfunction "SERIAL2_TX_36") (pintype "bidirectional"))
      (node (ref "D10") (pin "1") (pinfunction "C_1") (pintype "bidirectional"))
      (node (ref "R37") (pin "2") (pinfunction "2_2") (pintype "passive"))
    )
    (net (code "61") (name "SERIAL3_RX") (class "Default")
      (node (ref "CON1") (pin "20") (pinfunction "SERIAL3_RX_20") (pintype "bidirectional"))
      (node (ref "CON35") (pin "6") (pinfunction "6_6") (pintype "bidirectional"))
    )
    (net (code "62") (name "SERIAL3_TX") (class "Default")
      (node (ref "CON1") (pin "22") (pinfunction "SERIAL3_TX_22") (pintype "bidirectional"))
      (node (ref "CON35") (pin "5") (pinfunction "5_5") (pintype "bidirectional"))
    )
    (net (code "63") (name "SERIAL4_RX") (class "Default")
      (node (ref "CON1") (pin "16") (pinfunction "SERIAL4_RX_16") (pintype "bidirectional"))
      (node (ref "CON11") (pin "4") (pinfunction "4_4") (pintype "bidirectional"))
    )
    (net (code "64") (name "SERIAL4_TX") (class "Default")
      (node (ref "CON1") (pin "18") (pinfunction "SERIAL4_TX_18") (pintype "bidirectional"))
      (node (ref "CON11") (pin "3") (pinfunction "3_3") (pintype "bidirectional"))
    )
    (net (code "65") (name "SERIAL5_RX") (class "Default")
      (node (ref "CON1") (pin "12") (pinfunction "SERIAL5_RX_12") (pintype "bidirectional"))
      (node (ref "CON30") (pin "4") (pinfunction "4_4") (pintype "bidirectional"))
    )
    (net (code "66") (name "SERIAL5_TX") (class "Default")
      (node (ref "CON1") (pin "14") (pinfunction "SERIAL5_TX_14") (pintype "bidirectional"))
      (node (ref "CON30") (pin "3") (pinfunction "3_3") (pintype "bidirectional"))
    )
    (net (code "67") (name "TX_2") (class "Default")
      (node (ref "CON29") (pin "4") (pinfunction "4_4") (pintype "bidirectional"))
      (node (ref "MODULE1") (pin "15") (pinfunction "TX_2_15") (pintype "bidirectional"))
    )
    (net (code "68") (name "TX_3") (class "Default")
      (node (ref "CON32") (pin "4") (pinfunction "4_4") (pintype "bidirectional"))
      (node (ref "MODULE1") (pin "11") (pinfunction "TX_3_11") (pintype "bidirectional"))
    )
    (net (code "69") (name "TX_4") (class "Default")
      (node (ref "CON5") (pin "4") (pinfunction "4_4") (pintype "bidirectional"))
      (node (ref "MODULE1") (pin "7") (pinfunction "TX_4_7") (pintype "bidirectional"))
    )
    (net (code "70") (name "VBUS") (class "Default")
      (node (ref "CON1") (pin "29") (pinfunction "VBUS_29") (pintype "bidirectional"))
      (node (ref "CON14") (pin "2") (pinfunction "2_2") (pintype "passive"))
      (node (ref "CON19") (pin "A4") (pinfunction "VBUS_A4") (pintype "bidirectional"))
      (node (ref "CON19") (pin "B4") (pinfunction "VBUS_B4") (pintype "bidirectional"))
      (node (ref "D1") (pin "A") (pinfunction "A_A") (pintype "passive"))
    )
    (net (code "71") (name "unconnected-(CON1-3.3V_SPEKTRUM_EN-Pad19)") (class "Default")
      (node (ref "CON1") (pin "19") (pinfunction "3.3V_SPEKTRUM_EN_19") (pintype "bidirectional"))
    )
    (net (code "72") (name "unconnected-(CON1-AUX_BATT_CURRENT_SENS-Pad25)") (class "Default")
      (node (ref "CON1") (pin "25") (pinfunction "AUX_BATT_CURRENT_SENS_25") (pintype "bidirectional"))
    )
    (net (code "73") (name "unconnected-(CON1-AUX_BATT_VOLTAGE_SENS-Pad23)") (class "Default")
      (node (ref "CON1") (pin "23") (pinfunction "AUX_BATT_VOLTAGE_SENS_23") (pintype "bidirectional"))
    )
    (net (code "74") (name "unconnected-(CON1-CAN3_H-Pad10)") (class "Default")
      (node (ref "CON1") (pin "10") (pinfunction "CAN3_H_10") (pintype "bidirectional"))
    )
    (net (code "75") (name "unconnected-(CON1-CAN3_L-Pad8)") (class "Default")
      (node (ref "CON1") (pin "8") (pinfunction "CAN3_L_8") (pintype "bidirectional"))
    )
    (net (code "76") (name "unconnected-(CON1-EXTERN_DRDY-Pad11)") (class "Default")
      (node (ref "CON1") (pin "11") (pinfunction "EXTERN_DRDY_11") (pintype "bidirectional"))
    )
    (net (code "77") (name "unconnected-(CON1-FMU-SWCLK-Pad3)") (class "Default")
      (node (ref "CON1") (pin "3") (pinfunction "FMU-SWCLK_3") (pintype "bidirectional"))
    )
    (net (code "78") (name "unconnected-(CON1-FMU-SWDIO-Pad1)") (class "Default")
      (node (ref "CON1") (pin "1") (pinfunction "FMU-SWDIO_1") (pintype "bidirectional"))
    )
    (net (code "79") (name "unconnected-(CON1-FMU-~{RESET}-Pad7)") (class "Default")
      (node (ref "CON1") (pin "7") (pinfunction "FMU-~{RESET}_7") (pintype "bidirectional"))
    )
    (net (code "80") (name "unconnected-(CON1-I2C1_SCL-Pad37)") (class "Default")
      (node (ref "CON1") (pin "37") (pinfunction "I2C1_SCL_37") (pintype "bidirectional"))
    )
    (net (code "81") (name "unconnected-(CON1-I2C1_SDA-Pad35)") (class "Default")
      (node (ref "CON1") (pin "35") (pinfunction "I2C1_SDA_35") (pintype "bidirectional"))
    )
    (net (code "82") (name "unconnected-(CON1-IO-CH1-PROT-Pad80)") (class "Default")
      (node (ref "CON1") (pin "80") (pinfunction "IO-CH1-PROT_80") (pintype "bidirectional"))
    )
    (net (code "83") (name "unconnected-(CON1-IO-CH2-PROT-Pad78)") (class "Default")
      (node (ref "CON1") (pin "78") (pinfunction "IO-CH2-PROT_78") (pintype "bidirectional"))
    )
    (net (code "84") (name "unconnected-(CON1-IO-CH3-PROT-Pad76)") (class "Default")
      (node (ref "CON1") (pin "76") (pinfunction "IO-CH3-PROT_76") (pintype "bidirectional"))
    )
    (net (code "85") (name "unconnected-(CON1-IO-CH4-PROT-Pad74)") (class "Default")
      (node (ref "CON1") (pin "74") (pinfunction "IO-CH4-PROT_74") (pintype "bidirectional"))
    )
    (net (code "86") (name "unconnected-(CON1-IO-CH5-PROT-Pad72)") (class "Default")
      (node (ref "CON1") (pin "72") (pinfunction "IO-CH5-PROT_72") (pintype "bidirectional"))
    )
    (net (code "87") (name "unconnected-(CON1-IO-CH6-PROT-Pad70)") (class "Default")
      (node (ref "CON1") (pin "70") (pinfunction "IO-CH6-PROT_70") (pintype "bidirectional"))
    )
    (net (code "88") (name "unconnected-(CON1-IO-CH7-PROT-Pad68)") (class "Default")
      (node (ref "CON1") (pin "68") (pinfunction "IO-CH7-PROT_68") (pintype "bidirectional"))
    )
    (net (code "89") (name "unconnected-(CON1-IO-CH8-PROT-Pad66)") (class "Default")
      (node (ref "CON1") (pin "66") (pinfunction "IO-CH8-PROT_66") (pintype "bidirectional"))
    )
    (net (code "90") (name "unconnected-(CON1-IO-SWCLK-Pad71)") (class "Default")
      (node (ref "CON1") (pin "71") (pinfunction "IO-SWCLK_71") (pintype "bidirectional"))
    )
    (net (code "91") (name "unconnected-(CON1-IO-SWDIO-Pad69)") (class "Default")
      (node (ref "CON1") (pin "69") (pinfunction "IO-SWDIO_69") (pintype "bidirectional"))
    )
    (net (code "92") (name "unconnected-(CON1-IO-~{RESET}-Pad75)") (class "Default")
      (node (ref "CON1") (pin "75") (pinfunction "IO-~{RESET}_75") (pintype "bidirectional"))
    )
    (net (code "93") (name "unconnected-(CON1-IO_USART1_RX-Pad48)") (class "Default")
      (node (ref "CON1") (pin "48") (pinfunction "IO_USART1_RX_48") (pintype "bidirectional"))
    )
    (net (code "94") (name "unconnected-(CON1-IO_USART1_TX-Pad46)") (class "Default")
      (node (ref "CON1") (pin "46") (pinfunction "IO_USART1_TX_46") (pintype "bidirectional"))
    )
    (net (code "95") (name "unconnected-(CON1-IO_VDD_3V3-Pad26)") (class "Default")
      (node (ref "CON1") (pin "26") (pinfunction "IO_VDD_3V3_26") (pintype "bidirectional"))
    )
    (net (code "96") (name "unconnected-(CON1-IO_VDD_5V5-Pad65)") (class "Default")
      (node (ref "CON1") (pin "65") (pinfunction "IO_VDD_5V5_65") (pintype "bidirectional"))
    )
    (net (code "97") (name "unconnected-(CON1-PRESSURE_SENS_IN-Pad21)") (class "Default")
      (node (ref "CON1") (pin "21") (pinfunction "PRESSURE_SENS_IN_21") (pintype "bidirectional"))
    )
    (net (code "98") (name "unconnected-(CON1-S.BUS_OUT-Pad64)") (class "Default")
      (node (ref "CON1") (pin "64") (pinfunction "S.BUS_OUT_64") (pintype "bidirectional"))
    )
    (net (code "99") (name "unconnected-(CON1-SAFETY-Pad17)") (class "Default")
      (node (ref "CON1") (pin "17") (pinfunction "SAFETY_17") (pintype "bidirectional"))
    )
    (net (code "100") (name "unconnected-(CON1-SERIAL1_CTS-Pad44)") (class "Default")
      (node (ref "CON1") (pin "44") (pinfunction "SERIAL1_CTS_44") (pintype "bidirectional"))
    )
    (net (code "101") (name "unconnected-(CON1-SERIAL1_RTS-Pad42)") (class "Default")
      (node (ref "CON1") (pin "42") (pinfunction "SERIAL1_RTS_42") (pintype "bidirectional"))
    )
    (net (code "102") (name "unconnected-(CON1-SERIAL2_CTS-Pad32)") (class "Default")
      (node (ref "CON1") (pin "32") (pinfunction "SERIAL2_CTS_32") (pintype "bidirectional"))
    )
    (net (code "103") (name "unconnected-(CON1-SERIAL2_RTS-Pad30)") (class "Default")
      (node (ref "CON1") (pin "30") (pinfunction "SERIAL2_RTS_30") (pintype "bidirectional"))
    )
    (net (code "104") (name "unconnected-(CON1-SPI_EXT_MISO-Pad67)") (class "Default")
      (node (ref "CON1") (pin "67") (pinfunction "SPI_EXT_MISO_67") (pintype "bidirectional"))
    )
    (net (code "105") (name "unconnected-(CON1-SPI_EXT_MOSI-Pad51)") (class "Default")
      (node (ref "CON1") (pin "51") (pinfunction "SPI_EXT_MOSI_51") (pintype "bidirectional"))
    )
    (net (code "106") (name "unconnected-(CON1-SPI_EXT_SCK-Pad73)") (class "Default")
      (node (ref "CON1") (pin "73") (pinfunction "SPI_EXT_SCK_73") (pintype "bidirectional"))
    )
    (net (code "107") (name "unconnected-(CON1-VDD_SERVO-Pad53)") (class "Default")
      (node (ref "CON1") (pin "53") (pinfunction "VDD_SERVO_53") (pintype "bidirectional"))
    )
    (net (code "108") (name "unconnected-(CON1-VDD_SERVO_IN-Pad9)") (class "Default")
      (node (ref "CON1") (pin "9") (pinfunction "VDD_SERVO_IN_9") (pintype "bidirectional"))
    )
    (net (code "109") (name "unconnected-(CON1-~{EXTERN_CS}-Pad5)") (class "Default")
      (node (ref "CON1") (pin "5") (pinfunction "~{EXTERN_CS}_5") (pintype "bidirectional"))
    )
    (net (code "110") (name "unconnected-(CON1-~{IO-LED_SAFET_PROT}-Pad28)") (class "Default")
      (node (ref "CON1") (pin "28") (pinfunction "~{IO-LED_SAFET_PROT}_28") (pintype "bidirectional"))
    )
    (net (code "111") (name "unconnected-(CON1-~{VBUS_VALID}-Pad59)") (class "Default")
      (node (ref "CON1") (pin "59") (pinfunction "~{VBUS_VALID}_59") (pintype "bidirectional"))
    )
    (net (code "112") (name "unconnected-(CON1-~{VDD_5V_HIPOWER_OC}-Pad45)") (class "Default")
      (node (ref "CON1") (pin "45") (pinfunction "~{VDD_5V_HIPOWER_OC}_45") (pintype "bidirectional"))
    )
    (net (code "113") (name "unconnected-(CON1-~{VDD_5V_PERIPH_EN}-Pad27)") (class "Default")
      (node (ref "CON1") (pin "27") (pinfunction "~{VDD_5V_PERIPH_EN}_27") (pintype "bidirectional"))
    )
    (net (code "114") (name "unconnected-(CON1-~{VDD_5V_PERIPH_OC}-Pad43)") (class "Default")
      (node (ref "CON1") (pin "43") (pinfunction "~{VDD_5V_PERIPH_OC}_43") (pintype "bidirectional"))
    )
    (net (code "115") (name "unconnected-(CON1-~{VDD_BACKUP_VALID}-Pad57)") (class "Default")
      (node (ref "CON1") (pin "57") (pinfunction "~{VDD_BACKUP_VALID}_57") (pintype "bidirectional"))
    )
    (net (code "116") (name "unconnected-(MODULE1-CTS_5-Pad2)") (class "Default")
      (node (ref "MODULE1") (pin "2") (pinfunction "CTS_5_2") (pintype "bidirectional"))
    )
    (net (code "117") (name "unconnected-(MODULE1-RX_5-Pad1)") (class "Default")
      (node (ref "MODULE1") (pin "1") (pinfunction "RX_5_1") (pintype "bidirectional"))
    )
    (net (code "118") (name "unconnected-(MODULE1-TX_5-Pad3)") (class "Default")
      (node (ref "MODULE1") (pin "3") (pinfunction "TX_5_3") (pintype "bidirectional"))
    )
  )
)
